# 5v_ac_to_dc.net
KiCad netlist of a schematic drawn in EAGLE
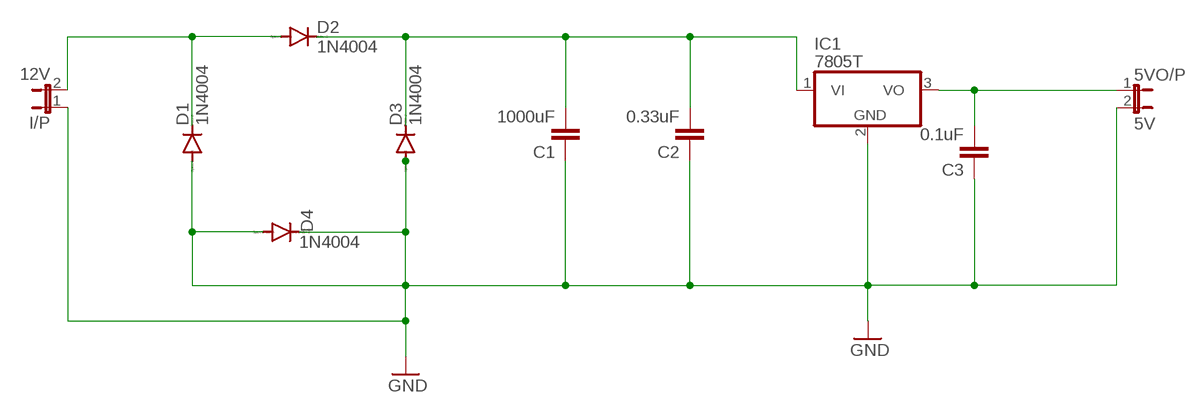
[diagram p0: schematic, sheet 1]

(export (version "E")
  (design (tool "Eeschema 10.0.6"))
  (components
    (comp (ref "5VO/P")
      (value "5V")
      (footprint "eagle-import:JP1")
      (libsource (lib "eagle-import") (part "JP1E"))
    )
    (comp (ref "C1")
      (value "1000uF")
      (footprint "eagle-import:C2.5-3")
      (libsource (lib "eagle-import") (part "C2,5-3"))
    )
    (comp (ref "C2")
      (value "0.33uF")
      (footprint "eagle-import:C2.5-3")
      (libsource (lib "eagle-import") (part "C2,5-3"))
    )
    (comp (ref "C3")
      (value "0.1uF")
      (footprint "eagle-import:C2.5-3")
      (libsource (lib "eagle-import") (part "C2,5-3"))
    )
    (comp (ref "D1")
      (value "1N4004")
      (footprint "eagle-import:DO41-10")
      (libsource (lib "eagle-import") (part "1N4004"))
    )
    (comp (ref "D2")
      (value "1N4004")
      (footprint "eagle-import:DO41-10")
      (libsource (lib "eagle-import") (part "1N4004"))
    )
    (comp (ref "D3")
      (value "1N4004")
      (footprint "eagle-import:DO41-10")
      (libsource (lib "eagle-import") (part "1N4004"))
    )
    (comp (ref "D4")
      (value "1N4004")
      (footprint "eagle-import:DO41-10")
      (libsource (lib "eagle-import") (part "1N4004"))
    )
    (comp (ref "I/P")
      (value "12V")
      (footprint "eagle-import:JP1")
      (libsource (lib "eagle-import") (part "JP1E"))
    )
    (comp (ref "IC1")
      (value "7805T")
      (footprint "eagle-import:TO220H")
      (libsource (lib "eagle-import") (part "78T05"))
    )
  )
  (nets
    (net (code "1") (name "GND") (class "Default")
      (node (ref "5VO/P") (pin "2") (pinfunction "2_2") (pintype "passive"))
      (node (ref "C1") (pin "1") (pinfunction "1_1") (pintype "passive"))
      (node (ref "C2") (pin "1") (pinfunction "1_1") (pintype "passive"))
      (node (ref "C3") (pin "1") (pinfunction "1_1") (pintype "passive"))
      (node (ref "D1") (pin "A") (pinfunction "A_A") (pintype "passive"))
      (node (ref "D3") (pin "A") (pinfunction "A_A") (pintype "passive"))
      (node (ref "D4") (pin "A") (pinfunction "A_A") (pintype "passive"))
      (node (ref "D4") (pin "C") (pinfunction "C_C") (pintype "passive"))
      (node (ref "I/P") (pin "1") (pinfunction "1_1") (pintype "passive"))
      (node (ref "IC1") (pin "2") (pinfunction "GND_2") (pintype "passive"))
    )
    (net (code "2") (name "Net-(D1-PadC)") (class "Default")
      (node (ref "D1") (pin "C") (pinfunction "C_C") (pintype "passive"))
      (node (ref "D2") (pin "A") (pinfunction "A_A") (pintype "passive"))
      (node (ref "I/P") (pin "2") (pinfunction "2_2") (pintype "passive"))
    )
    (net (code "3") (name "Net-(IC1-VI)") (class "Default")
      (node (ref "C1") (pin "2") (pinfunction "2_2") (pintype "passive"))
      (node (ref "C2") (pin "2") (pinfunction "2_2") (pintype "passive"))
      (node (ref "D2") (pin "C") (pinfunction "C_C") (pintype "passive"))
      (node (ref "D3") (pin "C") (pinfunction "C_C") (pintype "passive"))
      (node (ref "IC1") (pin "1") (pinfunction "VI_1") (pintype "input"))
    )
    (net (code "4") (name "Net-(IC1-VO)") (class "Default")
      (node (ref "5VO/P") (pin "1") (pinfunction "1_1") (pintype "passive"))
      (node (ref "C3") (pin "2") (pinfunction "2_2") (pintype "passive"))
      (node (ref "IC1") (pin "3") (pinfunction "VO_3") (pintype "passive"))
    )
  )
)
